# P1.net
KiCad netlist of a schematic drawn in EAGLE
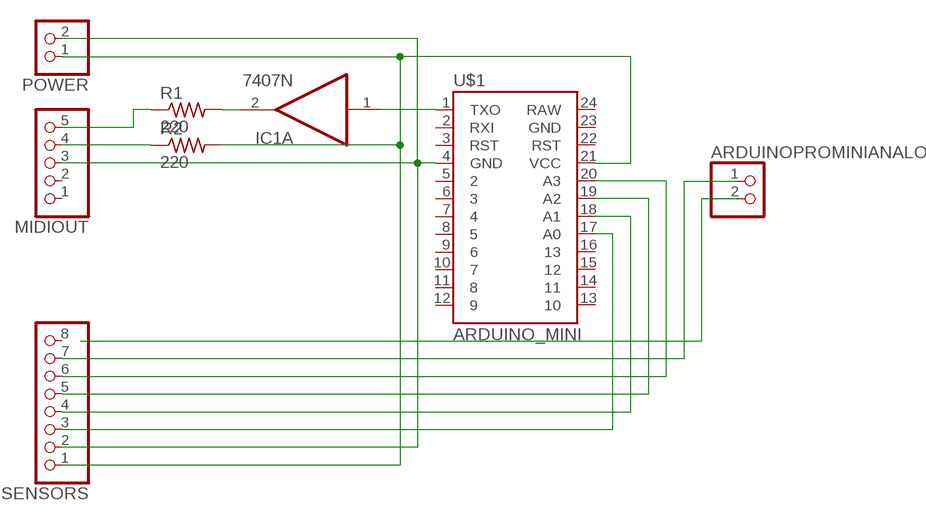
[diagram p0: schematic, sheet 1]

(export (version "E")
  (design (tool "Eeschema 10.0.6"))
  (components
    (comp (ref "ARDUINOPROMINIANALOG")
      (value "PINHD-1X2")
      (footprint "eagle-import:1X02")
      (libsource (lib "eagle-import") (part "PINHD-1X2"))
    )
    (comp (ref "IC1")
      (value "7407N")
      (footprint "eagle-import:DIL14")
      (libsource (lib "eagle-import") (part "7407N"))
    )
    (comp (ref "MIDIOUT")
      (value "PINHD-1X5")
      (footprint "eagle-import:1X05")
      (libsource (lib "eagle-import") (part "PINHD-1X5"))
    )
    (comp (ref "POWER")
      (value "PINHD-1X2")
      (footprint "eagle-import:1X02")
      (libsource (lib "eagle-import") (part "PINHD-1X2"))
    )
    (comp (ref "R1")
      (value "220")
      (footprint "eagle-import:0204_5")
      (libsource (lib "eagle-import") (part "R-US_0204/5"))
    )
    (comp (ref "R2")
      (value "220")
      (footprint "eagle-import:0204_5")
      (libsource (lib "eagle-import") (part "R-US_0204/5"))
    )
    (comp (ref "SENSORS")
      (value "PINHD-1X8")
      (footprint "eagle-import:1X08")
      (libsource (lib "eagle-import") (part "PINHD-1X8"))
    )
    (comp (ref "U$1")
      (value "ARDUINO_MINI")
      (footprint "eagle-import:ARDUINO_MINI")
      (libsource (lib "eagle-import") (part "ARDUINO_MINI"))
    )
  )
  (nets
    (net (code "1") (name "Net-(ARDUINOPROMINIANALOG-Pad1)") (class "Default")
      (node (ref "ARDUINOPROMINIANALOG") (pin "1") (pinfunction "1_1") (pintype "passive"))
      (node (ref "SENSORS") (pin "7") (pinfunction "7_7") (pintype "passive"))
    )
    (net (code "2") (name "Net-(IC1A-I)") (class "Default")
      (node (ref "IC1") (pin "1") (pinfunction "I_1") (pintype "input"))
      (node (ref "U$1") (pin "1") (pinfunction "TXO_1") (pintype "bidirectional"))
    )
    (net (code "3") (name "Net-(IC1A-O)") (class "Default")
      (node (ref "IC1") (pin "2") (pinfunction "O_2") (pintype "open_collector"))
      (node (ref "R1") (pin "2") (pinfunction "2_2") (pintype "passive"))
    )
    (net (code "4") (name "Net-(MIDIOUT-Pad3)") (class "Default")
      (node (ref "MIDIOUT") (pin "3") (pinfunction "3_3") (pintype "passive"))
      (node (ref "POWER") (pin "2") (pinfunction "2_2") (pintype "passive"))
      (node (ref "SENSORS") (pin "2") (pinfunction "2_2") (pintype "passive"))
      (node (ref "U$1") (pin "4") (pinfunction "GND_4") (pintype "bidirectional"))
    )
    (net (code "5") (name "Net-(MIDIOUT-Pad4)") (class "Default")
      (node (ref "MIDIOUT") (pin "4") (pinfunction "4_4") (pintype "passive"))
      (node (ref "R2") (pin "1") (pinfunction "1_1") (pintype "passive"))
    )
    (net (code "6") (name "Net-(MIDIOUT-Pad5)") (class "Default")
      (node (ref "MIDIOUT") (pin "5") (pinfunction "5_5") (pintype "passive"))
      (node (ref "R1") (pin "1") (pinfunction "1_1") (pintype "passive"))
    )
    (net (code "7") (name "Net-(U$1-A0)") (class "Default")
      (node (ref "SENSORS") (pin "3") (pinfunction "3_3") (pintype "passive"))
      (node (ref "U$1") (pin "17") (pinfunction "A0_17") (pintype "bidirectional"))
    )
    (net (code "8") (name "Net-(U$1-A1)") (class "Default")
      (node (ref "SENSORS") (pin "4") (pinfunction "4_4") (pintype "passive"))
      (node (ref "U$1") (pin "18") (pinfunction "A1_18") (pintype "bidirectional"))
    )
    (net (code "9") (name "Net-(U$1-A2)") (class "Default")
      (node (ref "SENSORS") (pin "5") (pinfunction "5_5") (pintype "passive"))
      (node (ref "U$1") (pin "19") (pinfunction "A2_19") (pintype "bidirectional"))
    )
    (net (code "10") (name "Net-(U$1-A3)") (class "Default")
      (node (ref "SENSORS") (pin "6") (pinfunction "6_6") (pintype "passive"))
      (node (ref "U$1") (pin "20") (pinfunction "A3_20") (pintype "bidirectional"))
    )
    (net (code "11") (name "Net-(U$1-VCC)") (class "Default")
      (node (ref "POWER") (pin "1") (pinfunction "1_1") (pintype "passive"))
      (node (ref "R2") (pin "2") (pinfunction "2_2") (pintype "passive"))
      (node (ref "SENSORS") (pin "1") (pinfunction "1_1") (pintype "passive"))
      (node (ref "U$1") (pin "21") (pinfunction "VCC_21") (pintype "bidirectional"))
    )
    (net (code "12") (name "unconnected-(ARDUINOPROMINIANALOG-Pad2)") (class "Default")
      (node (ref "ARDUINOPROMINIANALOG") (pin "2") (pinfunction "2_2") (pintype "passive"))
    )
    (net (code "13") (name "unconnected-(MIDIOUT-Pad1)") (class "Default")
      (node (ref "MIDIOUT") (pin "1") (pinfunction "1_1") (pintype "passive"))
    )
    (net (code "14") (name "unconnected-(MIDIOUT-Pad2)") (class "Default")
      (node (ref "MIDIOUT") (pin "2") (pinfunction "2_2") (pintype "passive"))
    )
    (net (code "15") (name "unconnected-(SENSORS-Pad8)") (class "Default")
      (node (ref "SENSORS") (pin "8") (pinfunction "8_8") (pintype "passive"))
    )
    (net (code "16") (name "unconnected-(U$1-2-Pad5)") (class "Default")
      (node (ref "U$1") (pin "5") (pinfunction "2_5") (pintype "bidirectional"))
    )
    (net (code "17") (name "unconnected-(U$1-3-Pad6)") (class "Default")
      (node (ref "U$1") (pin "6") (pinfunction "3_6") (pintype "bidirectional"))
    )
    (net (code "18") (name "unconnected-(U$1-4-Pad7)") (class "Default")
      (node (ref "U$1") (pin "7") (pinfunction "4_7") (pintype "bidirectional"))
    )
    (net (code "19") (name "unconnected-(U$1-5-Pad8)") (class "Default")
      (node (ref "U$1") (pin "8") (pinfunction "5_8") (pintype "bidirectional"))
    )
    (net (code "20") (name "unconnected-(U$1-6-Pad9)") (class "Default")
      (node (ref "U$1") (pin "9") (pinfunction "6_9") (pintype "bidirectional"))
    )
    (net (code "21") (name "unconnected-(U$1-7-Pad10)") (class "Default")
      (node (ref "U$1") (pin "10") (pinfunction "7_10") (pintype "bidirectional"))
    )
    (net (code "22") (name "unconnected-(U$1-8-Pad11)") (class "Default")
      (node (ref "U$1") (pin "11") (pinfunction "8_11") (pintype "bidirectional"))
    )
    (net (code "23") (name "unconnected-(U$1-9-Pad12)") (class "Default")
      (node (ref "U$1") (pin "12") (pinfunction "9_12") (pintype "bidirectional"))
    )
    (net (code "24") (name "unconnected-(U$1-10-Pad13)") (class "Default")
      (node (ref "U$1") (pin "13") (pinfunction "10_13") (pintype "bidirectional"))
    )
    (net (code "25") (name "unconnected-(U$1-11-Pad14)") (class "Default")
      (node (ref "U$1") (pin "14") (pinfunction "11_14") (pintype "bidirectional"))
    )
    (net (code "26") (name "unconnected-(U$1-12-Pad15)") (class "Default")
      (node (ref "U$1") (pin "15") (pinfunction "12_15") (pintype "bidirectional"))
    )
    (net (code "27") (name "unconnected-(U$1-13-Pad16)") (class "Default")
      (node (ref "U$1") (pin "16") (pinfunction "13_16") (pintype "bidirectional"))
    )
    (net (code "28") (name "unconnected-(U$1-GND-Pad23)") (class "Default")
      (node (ref "U$1") (pin "23") (pinfunction "GND_23") (pintype "bidirectional"))
    )
    (net (code "29") (name "unconnected-(U$1-RAW-Pad24)") (class "Default")
      (node (ref "U$1") (pin "24") (pinfunction "RAW_24") (pintype "bidirectional"))
    )
    (net (code "30") (name "unconnected-(U$1-RST-Pad3)") (class "Default")
      (node (ref "U$1") (pin "3") (pinfunction "RST_3") (pintype "bidirectional"))
    )
    (net (code "31") (name "unconnected-(U$1-RST-Pad22)") (class "Default")
      (node (ref "U$1") (pin "22") (pinfunction "RST_22") (pintype "bidirectional"))
    )
    (net (code "32") (name "unconnected-(U$1-RXI-Pad2)") (class "Default")
      (node (ref "U$1") (pin "2") (pinfunction "RXI_2") (pintype "bidirectional"))
    )
  )
)
